# Power.net
KiCad netlist of a schematic drawn in Altium Designer
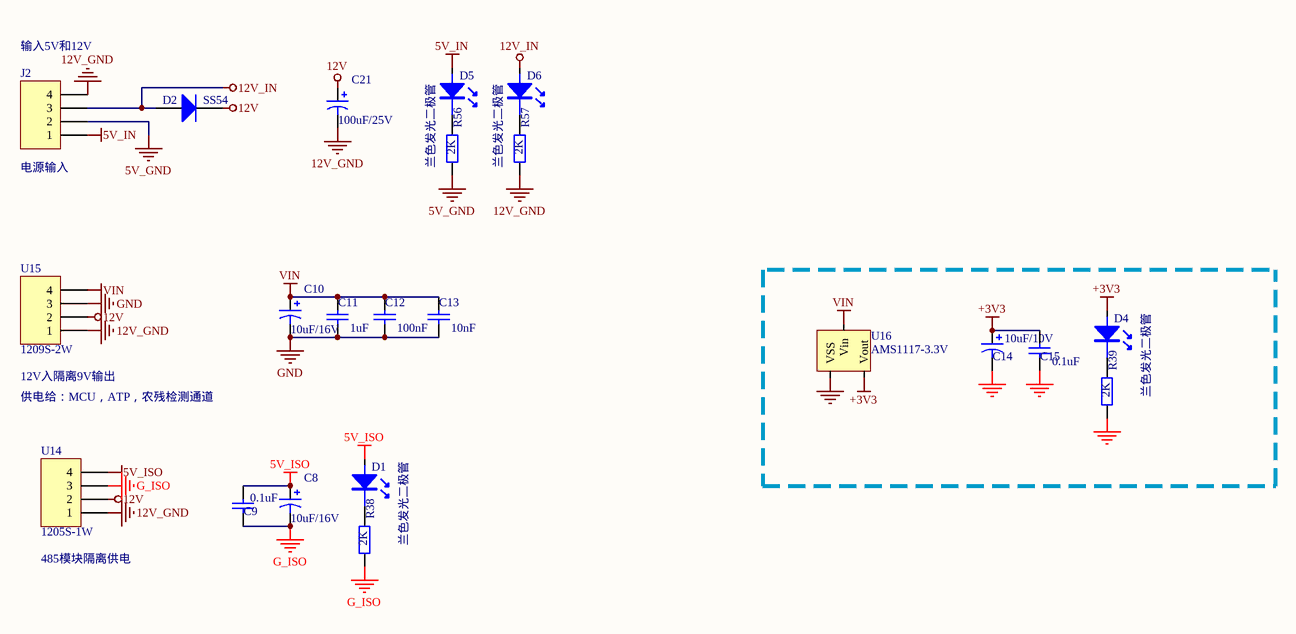
[diagram p0: Power.SchDoc]

(export (version "E")
  (design (tool "Eeschema 10.0.6"))
  (components
    (comp (ref "C8")
      (value "10uF/16V")
      (footprint "3216")
      (description "Polarized Capacitor (Radial)")
      (fields (field (name "PUBLISHER") "Altium Limited"))
      (libsource (lib "Miscellaneous Devices") (part "Cap Pol1"))
    )
    (comp (ref "C9")
      (value "0.1uF")
      (footprint "1608C")
      (description "Capacitor")
      (fields (field (name "PUBLISHER") "Altium Limited"))
      (libsource (lib "Miscellaneous Devices") (part "Cap"))
    )
    (comp (ref "C10")
      (value "10uF/16V")
      (footprint "3216")
      (description "Polarized Capacitor (Radial)")
      (fields (field (name "PUBLISHER") "Altium Limited"))
      (libsource (lib "Miscellaneous Devices") (part "Cap Pol1"))
    )
    (comp (ref "C11")
      (value "1uF")
      (footprint "1608C")
      (description "Capacitor")
      (fields (field (name "PUBLISHER") "Altium Limited"))
      (libsource (lib "Miscellaneous Devices") (part "Cap"))
    )
    (comp (ref "C12")
      (value "100nF")
      (footprint "1608C")
      (description "Capacitor")
      (fields (field (name "PUBLISHER") "Altium Limited"))
      (libsource (lib "Miscellaneous Devices") (part "Cap"))
    )
    (comp (ref "C13")
      (value "10nF")
      (footprint "1608C")
      (description "Capacitor")
      (fields (field (name "PUBLISHER") "Altium Limited"))
      (libsource (lib "Miscellaneous Devices") (part "Cap"))
    )
    (comp (ref "C14")
      (value "10uF/10V")
      (footprint "3216")
      (description "Polarized Capacitor (Radial)")
      (fields (field (name "PUBLISHER") "Altium Limited"))
      (libsource (lib "*") (part "Cap Pol1"))
    )
    (comp (ref "C15")
      (value "0.1uF")
      (footprint "1608C")
      (description "Capacitor")
      (fields (field (name "PUBLISHER") "Altium Limited"))
      (libsource (lib "Miscellaneous Devices") (part "Cap"))
    )
    (comp (ref "C21")
      (value "100uF/25V")
      (footprint "ECS6.3/6.6")
      (description "Polarized Capacitor (Radial)")
      (fields (field (name "PUBLISHER") "Altium Limited"))
      (libsource (lib "Miscellaneous Devices") (part "Cap Pol1"))
    )
    (comp (ref "D1") (value "兰色发光二极管") (footprint "LED/S") (libsource (lib "*") (part "LED")))
    (comp (ref "D2")
      (value "SS54")
      (footprint "SMA_DO-214AC")
      (description "Default Diode")
      (fields (field (name "PUBLISHER") "Altium Limited"))
      (libsource (lib "*") (part "Diode"))
    )
    (comp (ref "D4") (value "兰色发光二极管") (footprint "LED/S") (libsource (lib "*") (part "LED")))
    (comp (ref "D5") (value "兰色发光二极管") (footprint "LED/S") (libsource (lib "*") (part "LED")))
    (comp (ref "D6") (value "兰色发光二极管") (footprint "LED/S") (libsource (lib "*") (part "LED")))
    (comp (ref "J2")
      (value "电源输入")
      (footprint "KF2EDGV-5.08/4")
      (description "Header, 4-Pin")
      (fields (field (name "PUBLISHER") "Altium Limited"))
      (libsource (lib "Miscellaneous Connectors") (part "Header 4"))
    )
    (comp (ref "R38")
      (value "2K")
      (footprint "1608")
      (description "Resistor")
      (fields (field (name "PUBLISHER") "Altium Limited"))
      (libsource (lib "*") (part "Res2"))
    )
    (comp (ref "R39")
      (value "2K")
      (footprint "1608")
      (description "Resistor")
      (fields (field (name "PUBLISHER") "Altium Limited"))
      (libsource (lib "*") (part "Res2"))
    )
    (comp (ref "R56")
      (value "2K")
      (footprint "1608")
      (description "Resistor")
      (fields (field (name "PUBLISHER") "Altium Limited"))
      (libsource (lib "*") (part "Res2"))
    )
    (comp (ref "R57")
      (value "2K")
      (footprint "1608")
      (description "Resistor")
      (fields (field (name "PUBLISHER") "Altium Limited"))
      (libsource (lib "*") (part "Res2"))
    )
    (comp (ref "U14")
      (value "1205S-1W")
      (footprint "B0505S")
      (description "Header, 4-Pin")
      (fields (field (name "PUBLISHER") "Altium Limited"))
      (libsource (lib "Miscellaneous Connectors") (part "Header 4"))
    )
    (comp (ref "U15")
      (value "1209S-2W")
      (footprint "B0505S")
      (description "Header, 4-Pin")
      (fields (field (name "PUBLISHER") "Altium Limited"))
      (libsource (lib "Miscellaneous Connectors") (part "Header 4"))
    )
    (comp (ref "U16")
      (value "AMS1117-3.3V")
      (footprint "SOT223_L")
      (description "Header, 3-Pin")
      (fields (field (name "PUBLISHER") "Altium Limited"))
      (libsource (lib "Miscellaneous Connectors") (part "Header 3"))
    )
  )
  (nets
    (net (code "1") (name "+3V3") (class "Default")
      (node (ref "C14") (pin "1") (pinfunction "1_1") (pintype "passive"))
      (node (ref "C15") (pin "2") (pinfunction "2_2") (pintype "passive"))
      (node (ref "D4") (pin "A") (pinfunction "1_A") (pintype "passive"))
      (node (ref "U16") (pin "2") (pinfunction "Vout_2") (pintype "passive"))
    )
    (net (code "2") (name "5V_GND") (class "Default")
      (node (ref "J2") (pin "2") (pinfunction "2_2") (pintype "passive"))
      (node (ref "R56") (pin "2") (pinfunction "2_2") (pintype "passive"))
    )
    (net (code "3") (name "5V_IN") (class "Default")
      (node (ref "D5") (pin "A") (pinfunction "1_A") (pintype "passive"))
      (node (ref "J2") (pin "1") (pinfunction "1_1") (pintype "passive"))
    )
    (net (code "4") (name "5V_ISO") (class "Default")
      (node (ref "C8") (pin "1") (pinfunction "1_1") (pintype "passive"))
      (node (ref "C9") (pin "2") (pinfunction "2_2") (pintype "passive"))
      (node (ref "D1") (pin "A") (pinfunction "1_A") (pintype "passive"))
      (node (ref "U14") (pin "4") (pinfunction "4_4") (pintype "passive"))
    )
    (net (code "5") (name "12V") (class "Default")
      (node (ref "C21") (pin "1") (pinfunction "1_1") (pintype "passive"))
      (node (ref "D2") (pin "2") (pinfunction "K_2") (pintype "passive"))
      (node (ref "U14") (pin "2") (pinfunction "2_2") (pintype "passive"))
      (node (ref "U15") (pin "2") (pinfunction "2_2") (pintype "passive"))
    )
    (net (code "6") (name "12V_GND") (class "Default")
      (node (ref "C21") (pin "2") (pinfunction "2_2") (pintype "passive"))
      (node (ref "J2") (pin "4") (pinfunction "4_4") (pintype "passive"))
      (node (ref "R57") (pin "2") (pinfunction "2_2") (pintype "passive"))
      (node (ref "U14") (pin "1") (pinfunction "1_1") (pintype "passive"))
      (node (ref "U15") (pin "1") (pinfunction "1_1") (pintype "passive"))
    )
    (net (code "7") (name "12V_IN") (class "Default")
      (node (ref "D2") (pin "1") (pinfunction "A_1") (pintype "passive"))
      (node (ref "D6") (pin "A") (pinfunction "1_A") (pintype "passive"))
      (node (ref "J2") (pin "3") (pinfunction "3_3") (pintype "passive"))
    )
    (net (code "8") (name "GND") (class "Default")
      (node (ref "C10") (pin "2") (pinfunction "2_2") (pintype "passive"))
      (node (ref "C11") (pin "1") (pinfunction "1_1") (pintype "passive"))
      (node (ref "C12") (pin "1") (pinfunction "1_1") (pintype "passive"))
      (node (ref "C13") (pin "1") (pinfunction "1_1") (pintype "passive"))
      (node (ref "C14") (pin "2") (pinfunction "2_2") (pintype "passive"))
      (node (ref "C15") (pin "1") (pinfunction "1_1") (pintype "passive"))
      (node (ref "R39") (pin "2") (pinfunction "2_2") (pintype "passive"))
      (node (ref "U15") (pin "3") (pinfunction "3_3") (pintype "passive"))
      (node (ref "U16") (pin "1") (pinfunction "VSS_1") (pintype "passive"))
    )
    (net (code "9") (name "G_ISO") (class "Default")
      (node (ref "C8") (pin "2") (pinfunction "2_2") (pintype "passive"))
      (node (ref "C9") (pin "1") (pinfunction "1_1") (pintype "passive"))
      (node (ref "R38") (pin "2") (pinfunction "2_2") (pintype "passive"))
      (node (ref "U14") (pin "3") (pinfunction "3_3") (pintype "passive"))
    )
    (net (code "10") (name "Net-(D1-2)") (class "Default")
      (node (ref "D1") (pin "K") (pinfunction "2_K") (pintype "passive"))
      (node (ref "R38") (pin "1") (pinfunction "1_1") (pintype "passive"))
    )
    (net (code "11") (name "Net-(D4-2)") (class "Default")
      (node (ref "D4") (pin "K") (pinfunction "2_K") (pintype "passive"))
      (node (ref "R39") (pin "1") (pinfunction "1_1") (pintype "passive"))
    )
    (net (code "12") (name "Net-(D5-2)") (class "Default")
      (node (ref "D5") (pin "K") (pinfunction "2_K") (pintype "passive"))
      (node (ref "R56") (pin "1") (pinfunction "1_1") (pintype "passive"))
    )
    (net (code "13") (name "Net-(D6-2)") (class "Default")
      (node (ref "D6") (pin "K") (pinfunction "2_K") (pintype "passive"))
      (node (ref "R57") (pin "1") (pinfunction "1_1") (pintype "passive"))
    )
    (net (code "14") (name "VIN") (class "Default")
      (node (ref "C10") (pin "1") (pinfunction "1_1") (pintype "passive"))
      (node (ref "C11") (pin "2") (pinfunction "2_2") (pintype "passive"))
      (node (ref "C12") (pin "2") (pinfunction "2_2") (pintype "passive"))
      (node (ref "C13") (pin "2") (pinfunction "2_2") (pintype "passive"))
      (node (ref "U15") (pin "4") (pinfunction "4_4") (pintype "passive"))
      (node (ref "U16") (pin "3") (pinfunction "Vin_3") (pintype "passive"))
    )
  )
)
